# pcb-bldc-sensorless.net
KiCad netlist of a schematic drawn in EAGLE
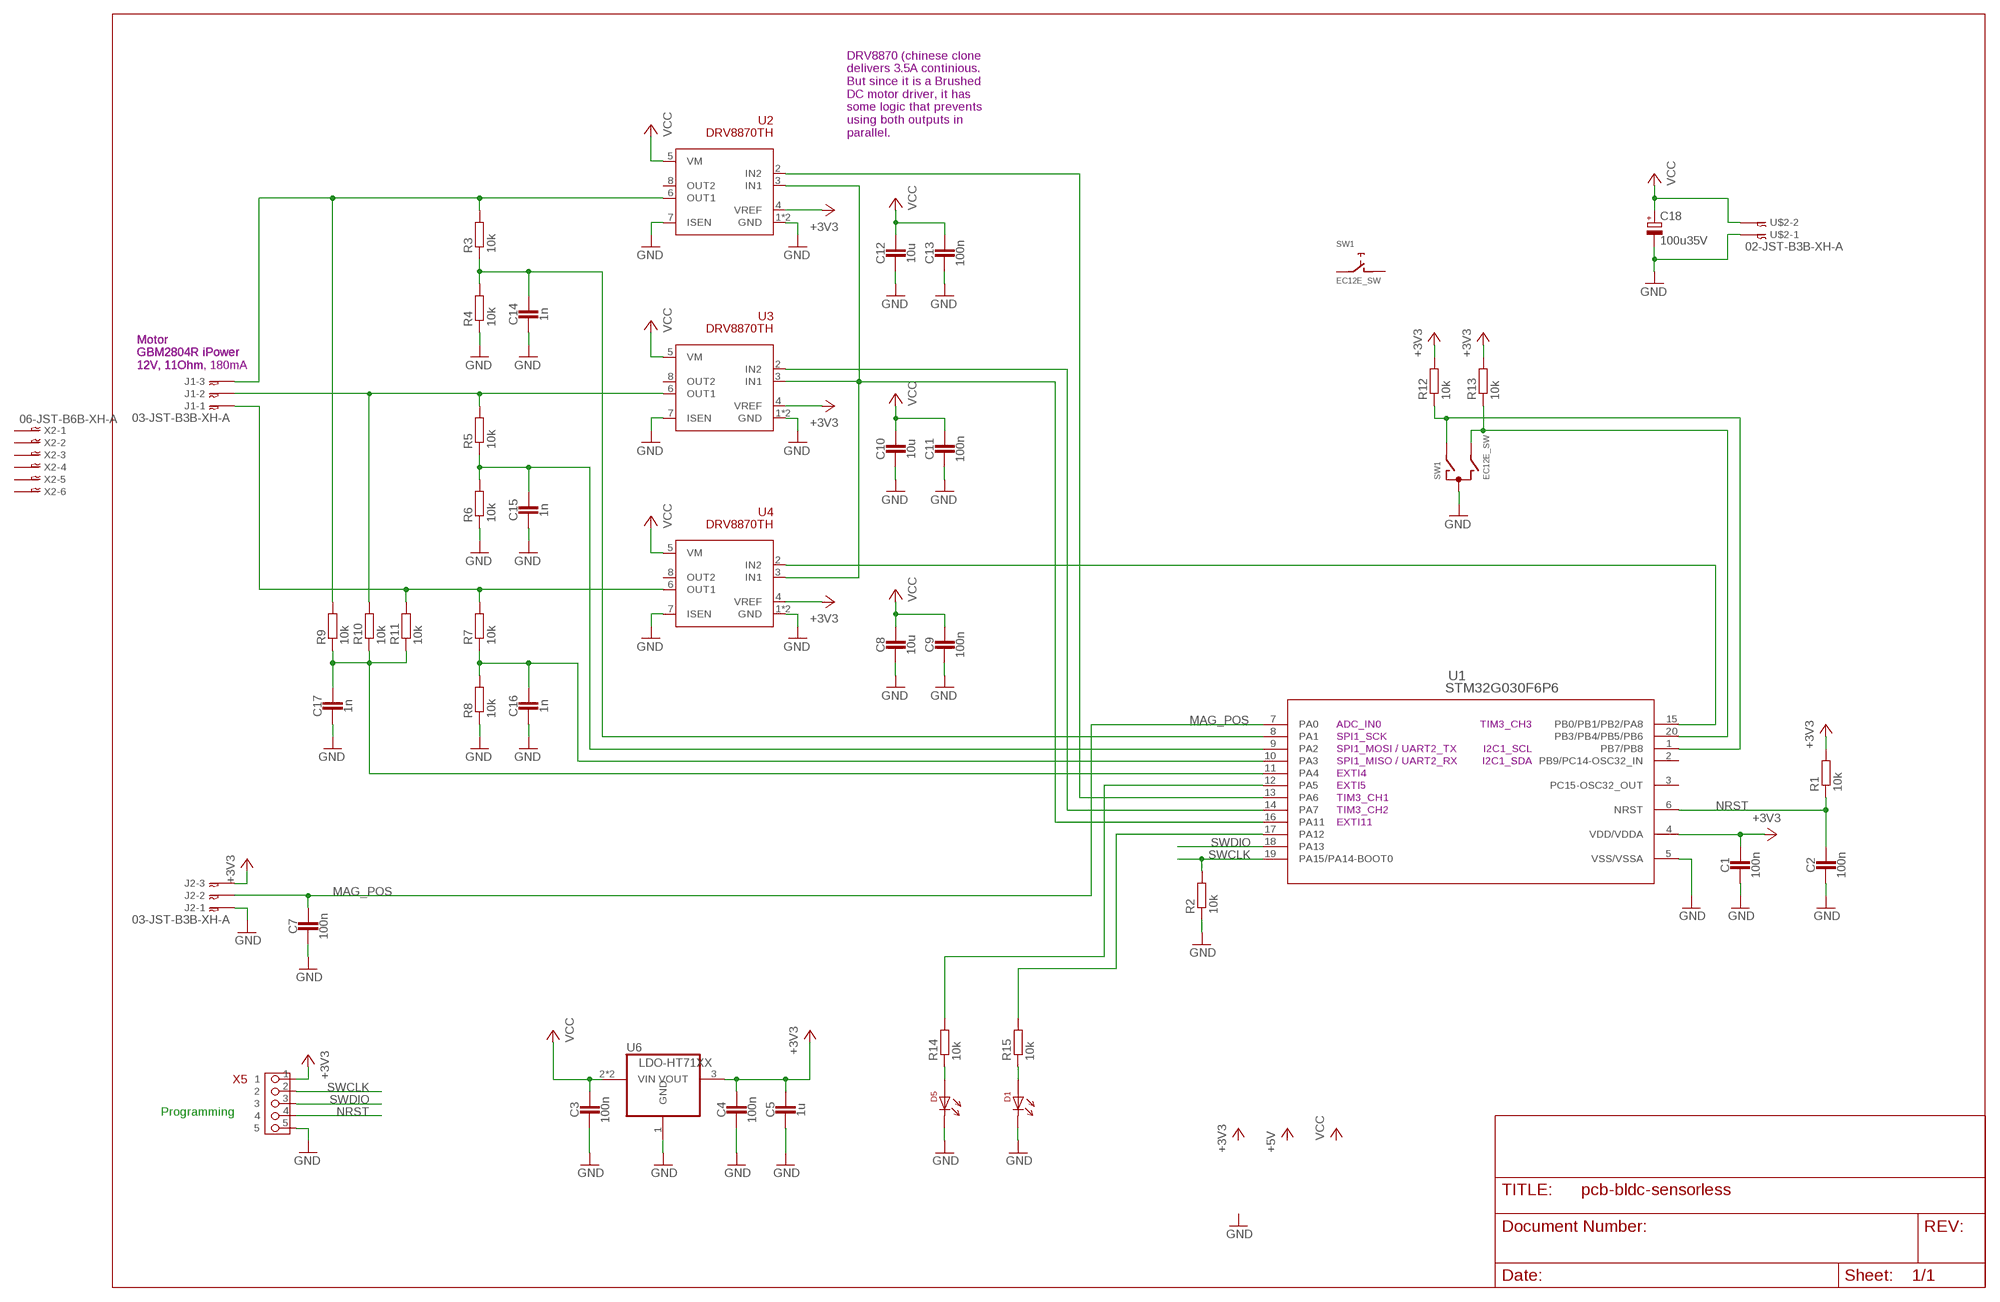
[diagram p0: schematic, sheet 1]

(export (version "E")
  (design (tool "Eeschema 10.0.6"))
  (components
    (comp (ref "C1")
      (value "100n")
      (footprint "eagle-import:0603_CAP")
      (libsource (lib "eagle-import") (part "CAPACITOR0603_CAP"))
    )
    (comp (ref "C2")
      (value "100n")
      (footprint "eagle-import:0603_CAP")
      (libsource (lib "eagle-import") (part "CAPACITOR0603_CAP"))
    )
    (comp (ref "C3")
      (value "100n")
      (footprint "eagle-import:0603_CAP")
      (libsource (lib "eagle-import") (part "CAPACITOR0603_CAP"))
    )
    (comp (ref "C4")
      (value "100n")
      (footprint "eagle-import:0603_CAP")
      (libsource (lib "eagle-import") (part "CAPACITOR0603_CAP"))
    )
    (comp (ref "C5")
      (value "1u")
      (footprint "eagle-import:0603_CAP")
      (libsource (lib "eagle-import") (part "CAPACITOR0603_CAP"))
    )
    (comp (ref "C7")
      (value "100n")
      (footprint "eagle-import:0603_CAP")
      (libsource (lib "eagle-import") (part "CAPACITOR0603_CAP"))
    )
    (comp (ref "C8")
      (value "10u")
      (footprint "eagle-import:1206_CAP")
      (libsource (lib "eagle-import") (part "CAPACITOR1206_CAP"))
    )
    (comp (ref "C9")
      (value "100n")
      (footprint "eagle-import:0603_CAP")
      (libsource (lib "eagle-import") (part "CAPACITOR0603_CAP"))
    )
    (comp (ref "C10")
      (value "10u")
      (footprint "eagle-import:1206_CAP")
      (libsource (lib "eagle-import") (part "CAPACITOR1206_CAP"))
    )
    (comp (ref "C11")
      (value "100n")
      (footprint "eagle-import:0603_CAP")
      (libsource (lib "eagle-import") (part "CAPACITOR0603_CAP"))
    )
    (comp (ref "C12")
      (value "10u")
      (footprint "eagle-import:1206_CAP")
      (libsource (lib "eagle-import") (part "CAPACITOR1206_CAP"))
    )
    (comp (ref "C13")
      (value "100n")
      (footprint "eagle-import:0603_CAP")
      (libsource (lib "eagle-import") (part "CAPACITOR0603_CAP"))
    )
    (comp (ref "C14")
      (value "1n")
      (footprint "eagle-import:0603_CAP")
      (libsource (lib "eagle-import") (part "CAPACITOR0603_CAP"))
    )
    (comp (ref "C15")
      (value "1n")
      (footprint "eagle-import:0603_CAP")
      (libsource (lib "eagle-import") (part "CAPACITOR0603_CAP"))
    )
    (comp (ref "C16")
      (value "1n")
      (footprint "eagle-import:0603_CAP")
      (libsource (lib "eagle-import") (part "CAPACITOR0603_CAP"))
    )
    (comp (ref "C17")
      (value "1n")
      (footprint "eagle-import:0603_CAP")
      (libsource (lib "eagle-import") (part "CAPACITOR0603_CAP"))
    )
    (comp (ref "C18")
      (value "100u35V")
      (footprint "eagle-import:153CLV-0605")
      (libsource (lib "eagle-import") (part "CPOL-EU153CLV-0605"))
    )
    (comp (ref "D1")
      (value "LED-0805")
      (footprint "eagle-import:0805-DOT")
      (libsource (lib "eagle-import") (part "LED-0805"))
    )
    (comp (ref "D5")
      (value "LED-0805")
      (footprint "eagle-import:0805-DOT")
      (libsource (lib "eagle-import") (part "LED-0805"))
    )
    (comp (ref "J1")
      (value "03-JST-B3B-XH-A")
      (footprint "eagle-import:B3B-XH")
      (libsource (lib "eagle-import") (part "03-JST-B3B-XH-A"))
    )
    (comp (ref "J2")
      (value "03-JST-B3B-XH-A")
      (footprint "eagle-import:B3B-XH")
      (libsource (lib "eagle-import") (part "03-JST-B3B-XH-A"))
    )
    (comp (ref "R1")
      (value "10k")
      (footprint "eagle-import:0603-RES")
      (libsource (lib "eagle-import") (part "RESISTOR0603_RES"))
    )
    (comp (ref "R2")
      (value "10k")
      (footprint "eagle-import:0603-RES")
      (libsource (lib "eagle-import") (part "RESISTOR0603_RES"))
    )
    (comp (ref "R3")
      (value "10k")
      (footprint "eagle-import:0603-RES")
      (libsource (lib "eagle-import") (part "RESISTOR0603_RES"))
    )
    (comp (ref "R4")
      (value "10k")
      (footprint "eagle-import:0603-RES")
      (libsource (lib "eagle-import") (part "RESISTOR0603_RES"))
    )
    (comp (ref "R5")
      (value "10k")
      (footprint "eagle-import:0603-RES")
      (libsource (lib "eagle-import") (part "RESISTOR0603_RES"))
    )
    (comp (ref "R6")
      (value "10k")
      (footprint "eagle-import:0603-RES")
      (libsource (lib "eagle-import") (part "RESISTOR0603_RES"))
    )
    (comp (ref "R7")
      (value "10k")
      (footprint "eagle-import:0603-RES")
      (libsource (lib "eagle-import") (part "RESISTOR0603_RES"))
    )
    (comp (ref "R8")
      (value "10k")
      (footprint "eagle-import:0603-RES")
      (libsource (lib "eagle-import") (part "RESISTOR0603_RES"))
    )
    (comp (ref "R9")
      (value "10k")
      (footprint "eagle-import:0603-RES")
      (libsource (lib "eagle-import") (part "RESISTOR0603_RES"))
    )
    (comp (ref "R10")
      (value "10k")
      (footprint "eagle-import:0603-RES")
      (libsource (lib "eagle-import") (part "RESISTOR0603_RES"))
    )
    (comp (ref "R11")
      (value "10k")
      (footprint "eagle-import:0603-RES")
      (libsource (lib "eagle-import") (part "RESISTOR0603_RES"))
    )
    (comp (ref "R12")
      (value "10k")
      (footprint "eagle-import:0603-RES")
      (libsource (lib "eagle-import") (part "RESISTOR0603_RES"))
    )
    (comp (ref "R13")
      (value "10k")
      (footprint "eagle-import:0603-RES")
      (libsource (lib "eagle-import") (part "RESISTOR0603_RES"))
    )
    (comp (ref "R14")
      (value "10k")
      (footprint "eagle-import:0603-RES")
      (libsource (lib "eagle-import") (part "RESISTOR0603_RES"))
    )
    (comp (ref "R15")
      (value "10k")
      (footprint "eagle-import:0603-RES")
      (libsource (lib "eagle-import") (part "RESISTOR0603_RES"))
    )
    (comp (ref "SW1")
      (value "EC12E_SW")
      (footprint "eagle-import:ALPS_EC12E_SW")
      (fields (field (name "MPN") "EC12E2424407"))
      (libsource (lib "eagle-import") (part "EC12E_SW"))
    )
    (comp (ref "U$2")
      (value "02-JST-B3B-XH-A")
      (footprint "eagle-import:B2B-XH")
      (libsource (lib "eagle-import") (part "02-JST-B3B-XH-A"))
    )
    (comp (ref "U1")
      (value "STM32G030F6P6")
      (footprint "eagle-import:TSSOP20")
      (fields (field (name "COPYRIGHT") "Copyright (C) 2024 Ultra Librarian. All rights reserved."))
      (libsource (lib "eagle-import") (part "STM32G030F6P6"))
    )
    (comp (ref "U2")
      (value "DRV8870TH")
      (footprint "eagle-import:SOIC-8-THERM")
      (libsource (lib "eagle-import") (part "DRV8870TH"))
    )
    (comp (ref "U3")
      (value "DRV8870TH")
      (footprint "eagle-import:SOIC-8-THERM")
      (libsource (lib "eagle-import") (part "DRV8870TH"))
    )
    (comp (ref "U4")
      (value "DRV8870TH")
      (footprint "eagle-import:SOIC-8-THERM")
      (libsource (lib "eagle-import") (part "DRV8870TH"))
    )
    (comp (ref "U6")
      (value "LDO-HT71XX")
      (footprint "eagle-import:SOT-89")
      (libsource (lib "eagle-import") (part "LDO-HT71XX"))
    )
    (comp (ref "X2")
      (value "06-JST-B6B-XH-A")
      (footprint "eagle-import:B6B-XH")
      (libsource (lib "eagle-import") (part "06-JST-B6B-XH-A"))
    )
    (comp (ref "X5")
      (value "PIN_5X1HD")
      (footprint "eagle-import:PIN_5X1_HD")
      (libsource (lib "eagle-import") (part "PIN_5X1HD"))
    )
  )
  (nets
    (net (code "1") (name "+3V3") (class "Default")
      (node (ref "C1") (pin "1") (pinfunction "1_1") (pintype "bidirectional"))
      (node (ref "C4") (pin "1") (pinfunction "1_1") (pintype "bidirectional"))
      (node (ref "C5") (pin "1") (pinfunction "1_1") (pintype "bidirectional"))
      (node (ref "J2") (pin "P$3") (pinfunction "1_P$3") (pintype "passive"))
      (node (ref "R1") (pin "2") (pinfunction "2_2") (pintype "passive"))
      (node (ref "R12") (pin "2") (pinfunction "2_2") (pintype "passive"))
      (node (ref "R13") (pin "2") (pinfunction "2_2") (pintype "passive"))
      (node (ref "U1") (pin "4") (pinfunction "VDD/VDDA_4") (pintype "power_in"))
      (node (ref "U2") (pin "4") (pinfunction "VREF_4") (pintype "bidirectional"))
      (node (ref "U3") (pin "4") (pinfunction "VREF_4") (pintype "bidirectional"))
      (node (ref "U4") (pin "4") (pinfunction "VREF_4") (pintype "bidirectional"))
      (node (ref "U6") (pin "3") (pinfunction "VOUT_3") (pintype "output"))
      (node (ref "X5") (pin "1") (pinfunction "1_1") (pintype "bidirectional"))
    )
    (net (code "3") (name "/MAG_POS") (class "Default")
      (node (ref "C7") (pin "1") (pinfunction "1_1") (pintype "bidirectional"))
      (node (ref "J2") (pin "P$2") (pinfunction "1_P$2") (pintype "passive"))
      (node (ref "U1") (pin "7") (pinfunction "PA0_7") (pintype "bidirectional"))
    )
    (net (code "4") (name "/NRST") (class "Default")
      (node (ref "C2") (pin "1") (pinfunction "1_1") (pintype "bidirectional"))
      (node (ref "R1") (pin "1") (pinfunction "1_1") (pintype "passive"))
      (node (ref "U1") (pin "6") (pinfunction "NRST_6") (pintype "bidirectional"))
      (node (ref "X5") (pin "4") (pinfunction "4_4") (pintype "bidirectional"))
    )
    (net (code "5") (name "/SWCLK") (class "Default")
      (node (ref "R2") (pin "2") (pinfunction "2_2") (pintype "passive"))
      (node (ref "U1") (pin "19") (pinfunction "PA15/PA14-BOOT0_19") (pintype "bidirectional"))
      (node (ref "X5") (pin "2") (pinfunction "2_2") (pintype "bidirectional"))
    )
    (net (code "6") (name "/SWDIO") (class "Default")
      (node (ref "U1") (pin "18") (pinfunction "PA13_18") (pintype "bidirectional"))
      (node (ref "X5") (pin "3") (pinfunction "3_3") (pintype "bidirectional"))
    )
    (net (code "7") (name "GND") (class "Default")
      (node (ref "C1") (pin "2") (pinfunction "2_2") (pintype "bidirectional"))
      (node (ref "C10") (pin "2") (pinfunction "2_2") (pintype "bidirectional"))
      (node (ref "C11") (pin "2") (pinfunction "2_2") (pintype "bidirectional"))
      (node (ref "C12") (pin "2") (pinfunction "2_2") (pintype "bidirectional"))
      (node (ref "C13") (pin "2") (pinfunction "2_2") (pintype "bidirectional"))
      (node (ref "C14") (pin "2") (pinfunction "2_2") (pintype "bidirectional"))
      (node (ref "C15") (pin "2") (pinfunction "2_2") (pintype "bidirectional"))
      (node (ref "C16") (pin "2") (pinfunction "2_2") (pintype "bidirectional"))
      (node (ref "C17") (pin "2") (pinfunction "2_2") (pintype "bidirectional"))
      (node (ref "C18") (pin "-") (pinfunction "-_-") (pintype "passive"))
      (node (ref "C2") (pin "2") (pinfunction "2_2") (pintype "bidirectional"))
      (node (ref "C3") (pin "2") (pinfunction "2_2") (pintype "bidirectional"))
      (node (ref "C4") (pin "2") (pinfunction "2_2") (pintype "bidirectional"))
      (node (ref "C5") (pin "2") (pinfunction "2_2") (pintype "bidirectional"))
      (node (ref "C7") (pin "2") (pinfunction "2_2") (pintype "bidirectional"))
      (node (ref "C8") (pin "2") (pinfunction "2_2") (pintype "bidirectional"))
      (node (ref "C9") (pin "2") (pinfunction "2_2") (pintype "bidirectional"))
      (node (ref "D1") (pin "2") (pinfunction "2_2") (pintype "bidirectional"))
      (node (ref "D5") (pin "2") (pinfunction "2_2") (pintype "bidirectional"))
      (node (ref "J2") (pin "P$1") (pinfunction "1_P$1") (pintype "passive"))
      (node (ref "R2") (pin "1") (pinfunction "1_1") (pintype "passive"))
      (node (ref "R4") (pin "1") (pinfunction "1_1") (pintype "passive"))
      (node (ref "R6") (pin "1") (pinfunction "1_1") (pintype "passive"))
      (node (ref "R8") (pin "1") (pinfunction "1_1") (pintype "passive"))
      (node (ref "SW1") (pin "C") (pinfunction "C_C") (pintype "passive"))
      (node (ref "U$2") (pin "P$1") (pinfunction "1_P$1") (pintype "passive"))
      (node (ref "U1") (pin "5") (pinfunction "VSS/VSSA_5") (pintype "power_in"))
      (node (ref "U2") (pin "1") (pinfunction "GND_1") (pintype "bidirectional"))
      (node (ref "U2") (pin "7") (pinfunction "ISEN_7") (pintype "bidirectional"))
      (node (ref "U2") (pin "9") (pinfunction "GND_9") (pintype "bidirectional"))
      (node (ref "U3") (pin "1") (pinfunction "GND_1") (pintype "bidirectional"))
      (node (ref "U3") (pin "7") (pinfunction "ISEN_7") (pintype "bidirectional"))
      (node (ref "U3") (pin "9") (pinfunction "GND_9") (pintype "bidirectional"))
      (node (ref "U4") (pin "1") (pinfunction "GND_1") (pintype "bidirectional"))
      (node (ref "U4") (pin "7") (pinfunction "ISEN_7") (pintype "bidirectional"))
      (node (ref "U4") (pin "9") (pinfunction "GND_9") (pintype "bidirectional"))
      (node (ref "U6") (pin "1") (pinfunction "GND_1") (pintype "power_in"))
      (node (ref "X5") (pin "5") (pinfunction "5_5") (pintype "bidirectional"))
    )
    (net (code "8") (name "Net-(D1-Pad1)") (class "Default")
      (node (ref "D1") (pin "1") (pinfunction "1_1") (pintype "bidirectional"))
      (node (ref "R15") (pin "1") (pinfunction "1_1") (pintype "passive"))
    )
    (net (code "9") (name "Net-(D5-Pad1)") (class "Default")
      (node (ref "D5") (pin "1") (pinfunction "1_1") (pintype "bidirectional"))
      (node (ref "R14") (pin "1") (pinfunction "1_1") (pintype "passive"))
    )
    (net (code "10") (name "Net-(J1A-1)") (class "Default")
      (node (ref "J1") (pin "P$1") (pinfunction "1_P$1") (pintype "passive"))
      (node (ref "R11") (pin "2") (pinfunction "2_2") (pintype "passive"))
      (node (ref "R7") (pin "2") (pinfunction "2_2") (pintype "passive"))
      (node (ref "U4") (pin "6") (pinfunction "OUT1_6") (pintype "bidirectional"))
    )
    (net (code "11") (name "Net-(J1B-1)") (class "Default")
      (node (ref "J1") (pin "P$2") (pinfunction "1_P$2") (pintype "passive"))
      (node (ref "R10") (pin "2") (pinfunction "2_2") (pintype "passive"))
      (node (ref "R5") (pin "2") (pinfunction "2_2") (pintype "passive"))
      (node (ref "U3") (pin "6") (pinfunction "OUT1_6") (pintype "bidirectional"))
    )
    (net (code "12") (name "Net-(J1C-1)") (class "Default")
      (node (ref "J1") (pin "P$3") (pinfunction "1_P$3") (pintype "passive"))
      (node (ref "R3") (pin "2") (pinfunction "2_2") (pintype "passive"))
      (node (ref "R9") (pin "2") (pinfunction "2_2") (pintype "passive"))
      (node (ref "U2") (pin "6") (pinfunction "OUT1_6") (pintype "bidirectional"))
    )
    (net (code "13") (name "Net-(U1-PA1)") (class "Default")
      (node (ref "C14") (pin "1") (pinfunction "1_1") (pintype "bidirectional"))
      (node (ref "R3") (pin "1") (pinfunction "1_1") (pintype "passive"))
      (node (ref "R4") (pin "2") (pinfunction "2_2") (pintype "passive"))
      (node (ref "U1") (pin "8") (pinfunction "PA1_8") (pintype "bidirectional"))
    )
    (net (code "14") (name "Net-(U1-PA2)") (class "Default")
      (node (ref "C15") (pin "1") (pinfunction "1_1") (pintype "bidirectional"))
      (node (ref "R5") (pin "1") (pinfunction "1_1") (pintype "passive"))
      (node (ref "R6") (pin "2") (pinfunction "2_2") (pintype "passive"))
      (node (ref "U1") (pin "9") (pinfunction "PA2_9") (pintype "bidirectional"))
    )
    (net (code "15") (name "Net-(U1-PA3)") (class "Default")
      (node (ref "C16") (pin "1") (pinfunction "1_1") (pintype "bidirectional"))
      (node (ref "R7") (pin "1") (pinfunction "1_1") (pintype "passive"))
      (node (ref "R8") (pin "2") (pinfunction "2_2") (pintype "passive"))
      (node (ref "U1") (pin "10") (pinfunction "PA3_10") (pintype "bidirectional"))
    )
    (net (code "16") (name "Net-(U1-PA4)") (class "Default")
      (node (ref "C17") (pin "1") (pinfunction "1_1") (pintype "bidirectional"))
      (node (ref "R10") (pin "1") (pinfunction "1_1") (pintype "passive"))
      (node (ref "R11") (pin "1") (pinfunction "1_1") (pintype "passive"))
      (node (ref "R9") (pin "1") (pinfunction "1_1") (pintype "passive"))
      (node (ref "U1") (pin "11") (pinfunction "PA4_11") (pintype "bidirectional"))
    )
    (net (code "17") (name "Net-(U1-PA5)") (class "Default")
      (node (ref "R14") (pin "2") (pinfunction "2_2") (pintype "passive"))
      (node (ref "U1") (pin "12") (pinfunction "PA5_12") (pintype "bidirectional"))
    )
    (net (code "18") (name "Net-(U1-PA6)") (class "Default")
      (node (ref "U1") (pin "13") (pinfunction "PA6_13") (pintype "bidirectional"))
      (node (ref "U2") (pin "2") (pinfunction "IN2_2") (pintype "bidirectional"))
    )
    (net (code "19") (name "Net-(U1-PA7)") (class "Default")
      (node (ref "U1") (pin "14") (pinfunction "PA7_14") (pintype "bidirectional"))
      (node (ref "U3") (pin "2") (pinfunction "IN2_2") (pintype "bidirectional"))
    )
    (net (code "20") (name "Net-(U1-PA11)") (class "Default")
      (node (ref "U1") (pin "16") (pinfunction "PA11_16") (pintype "bidirectional"))
      (node (ref "U2") (pin "3") (pinfunction "IN1_3") (pintype "bidirectional"))
      (node (ref "U3") (pin "3") (pinfunction "IN1_3") (pintype "bidirectional"))
      (node (ref "U4") (pin "3") (pinfunction "IN1_3") (pintype "bidirectional"))
    )
    (net (code "21") (name "Net-(U1-PA12)") (class "Default")
      (node (ref "R15") (pin "2") (pinfunction "2_2") (pintype "passive"))
      (node (ref "U1") (pin "17") (pinfunction "PA12_17") (pintype "bidirectional"))
    )
    (net (code "22") (name "Net-(U1-PB0{slash}PB1{slash}PB2{slash}PA8)") (class "Default")
      (node (ref "U1") (pin "15") (pinfunction "PB0/PB1/PB2/PA8_15") (pintype "bidirectional"))
      (node (ref "U4") (pin "2") (pinfunction "IN2_2") (pintype "bidirectional"))
    )
    (net (code "23") (name "Net-(U1-PB3{slash}PB4{slash}PB5{slash}PB6)") (class "Default")
      (node (ref "R13") (pin "1") (pinfunction "1_1") (pintype "passive"))
      (node (ref "SW1") (pin "B") (pinfunction "B_B") (pintype "passive"))
      (node (ref "U1") (pin "20") (pinfunction "PB3/PB4/PB5/PB6_20") (pintype "bidirectional"))
    )
    (net (code "24") (name "Net-(U1-PB7{slash}PB8)") (class "Default")
      (node (ref "R12") (pin "1") (pinfunction "1_1") (pintype "passive"))
      (node (ref "SW1") (pin "A") (pinfunction "A_A") (pintype "passive"))
      (node (ref "U1") (pin "1") (pinfunction "PB7/PB8_1") (pintype "bidirectional"))
    )
    (net (code "25") (name "VCC") (class "Default")
      (node (ref "C10") (pin "1") (pinfunction "1_1") (pintype "bidirectional"))
      (node (ref "C11") (pin "1") (pinfunction "1_1") (pintype "bidirectional"))
      (node (ref "C12") (pin "1") (pinfunction "1_1") (pintype "bidirectional"))
      (node (ref "C13") (pin "1") (pinfunction "1_1") (pintype "bidirectional"))
      (node (ref "C18") (pin "+") (pinfunction "+_+") (pintype "passive"))
      (node (ref "C3") (pin "1") (pinfunction "1_1") (pintype "bidirectional"))
      (node (ref "C8") (pin "1") (pinfunction "1_1") (pintype "bidirectional"))
      (node (ref "C9") (pin "1") (pinfunction "1_1") (pintype "bidirectional"))
      (node (ref "U$2") (pin "P$2") (pinfunction "1_P$2") (pintype "passive"))
      (node (ref "U2") (pin "5") (pinfunction "VM_5") (pintype "bidirectional"))
      (node (ref "U3") (pin "5") (pinfunction "VM_5") (pintype "bidirectional"))
      (node (ref "U4") (pin "5") (pinfunction "VM_5") (pintype "bidirectional"))
      (node (ref "U6") (pin "2") (pinfunction "VIN_2") (pintype "input"))
      (node (ref "U6") (pin "2@1") (pinfunction "VIN_2@1") (pintype "input"))
    )
    (net (code "26") (name "unconnected-(SW1B-1-PadD)") (class "Default")
      (node (ref "SW1") (pin "D") (pinfunction "1_D") (pintype "passive"))
    )
    (net (code "27") (name "unconnected-(SW1B-2-PadE)") (class "Default")
      (node (ref "SW1") (pin "E") (pinfunction "2_E") (pintype "passive"))
    )
    (net (code "28") (name "unconnected-(U1-PB9{slash}PC14-OSC32_IN-Pad2)") (class "Default")
      (node (ref "U1") (pin "2") (pinfunction "PB9/PC14-OSC32_IN_2") (pintype "bidirectional"))
    )
    (net (code "29") (name "unconnected-(U1-PC15-OSC32_OUT-Pad3)") (class "Default")
      (node (ref "U1") (pin "3") (pinfunction "PC15-OSC32_OUT_3") (pintype "bidirectional"))
    )
    (net (code "30") (name "unconnected-(U2-OUT2-Pad8)") (class "Default")
      (node (ref "U2") (pin "8") (pinfunction "OUT2_8") (pintype "bidirectional"))
    )
    (net (code "31") (name "unconnected-(U3-OUT2-Pad8)") (class "Default")
      (node (ref "U3") (pin "8") (pinfunction "OUT2_8") (pintype "bidirectional"))
    )
    (net (code "32") (name "unconnected-(U4-OUT2-Pad8)") (class "Default")
      (node (ref "U4") (pin "8") (pinfunction "OUT2_8") (pintype "bidirectional"))
    )
    (net (code "33") (name "unconnected-(X2A-1-PadP$1)") (class "Default")
      (node (ref "X2") (pin "P$1") (pinfunction "1_P$1") (pintype "passive"))
    )
    (net (code "34") (name "unconnected-(X2B-1-PadP$2)") (class "Default")
      (node (ref "X2") (pin "P$2") (pinfunction "1_P$2") (pintype "passive"))
    )
    (net (code "35") (name "unconnected-(X2C-1-PadP$3)") (class "Default")
      (node (ref "X2") (pin "P$3") (pinfunction "1_P$3") (pintype "passive"))
    )
    (net (code "36") (name "unconnected-(X2D-1-PadP$4)") (class "Default")
      (node (ref "X2") (pin "P$4") (pinfunction "1_P$4") (pintype "passive"))
    )
    (net (code "37") (name "unconnected-(X2E-1-PadP$5)") (class "Default")
      (node (ref "X2") (pin "P$5") (pinfunction "1_P$5") (pintype "passive"))
    )
    (net (code "38") (name "unconnected-(X2F-1-PadP$6)") (class "Default")
      (node (ref "X2") (pin "P$6") (pinfunction "1_P$6") (pintype "passive"))
    )
  )
)
